# ax12.net
KiCad netlist of a schematic drawn in EAGLE
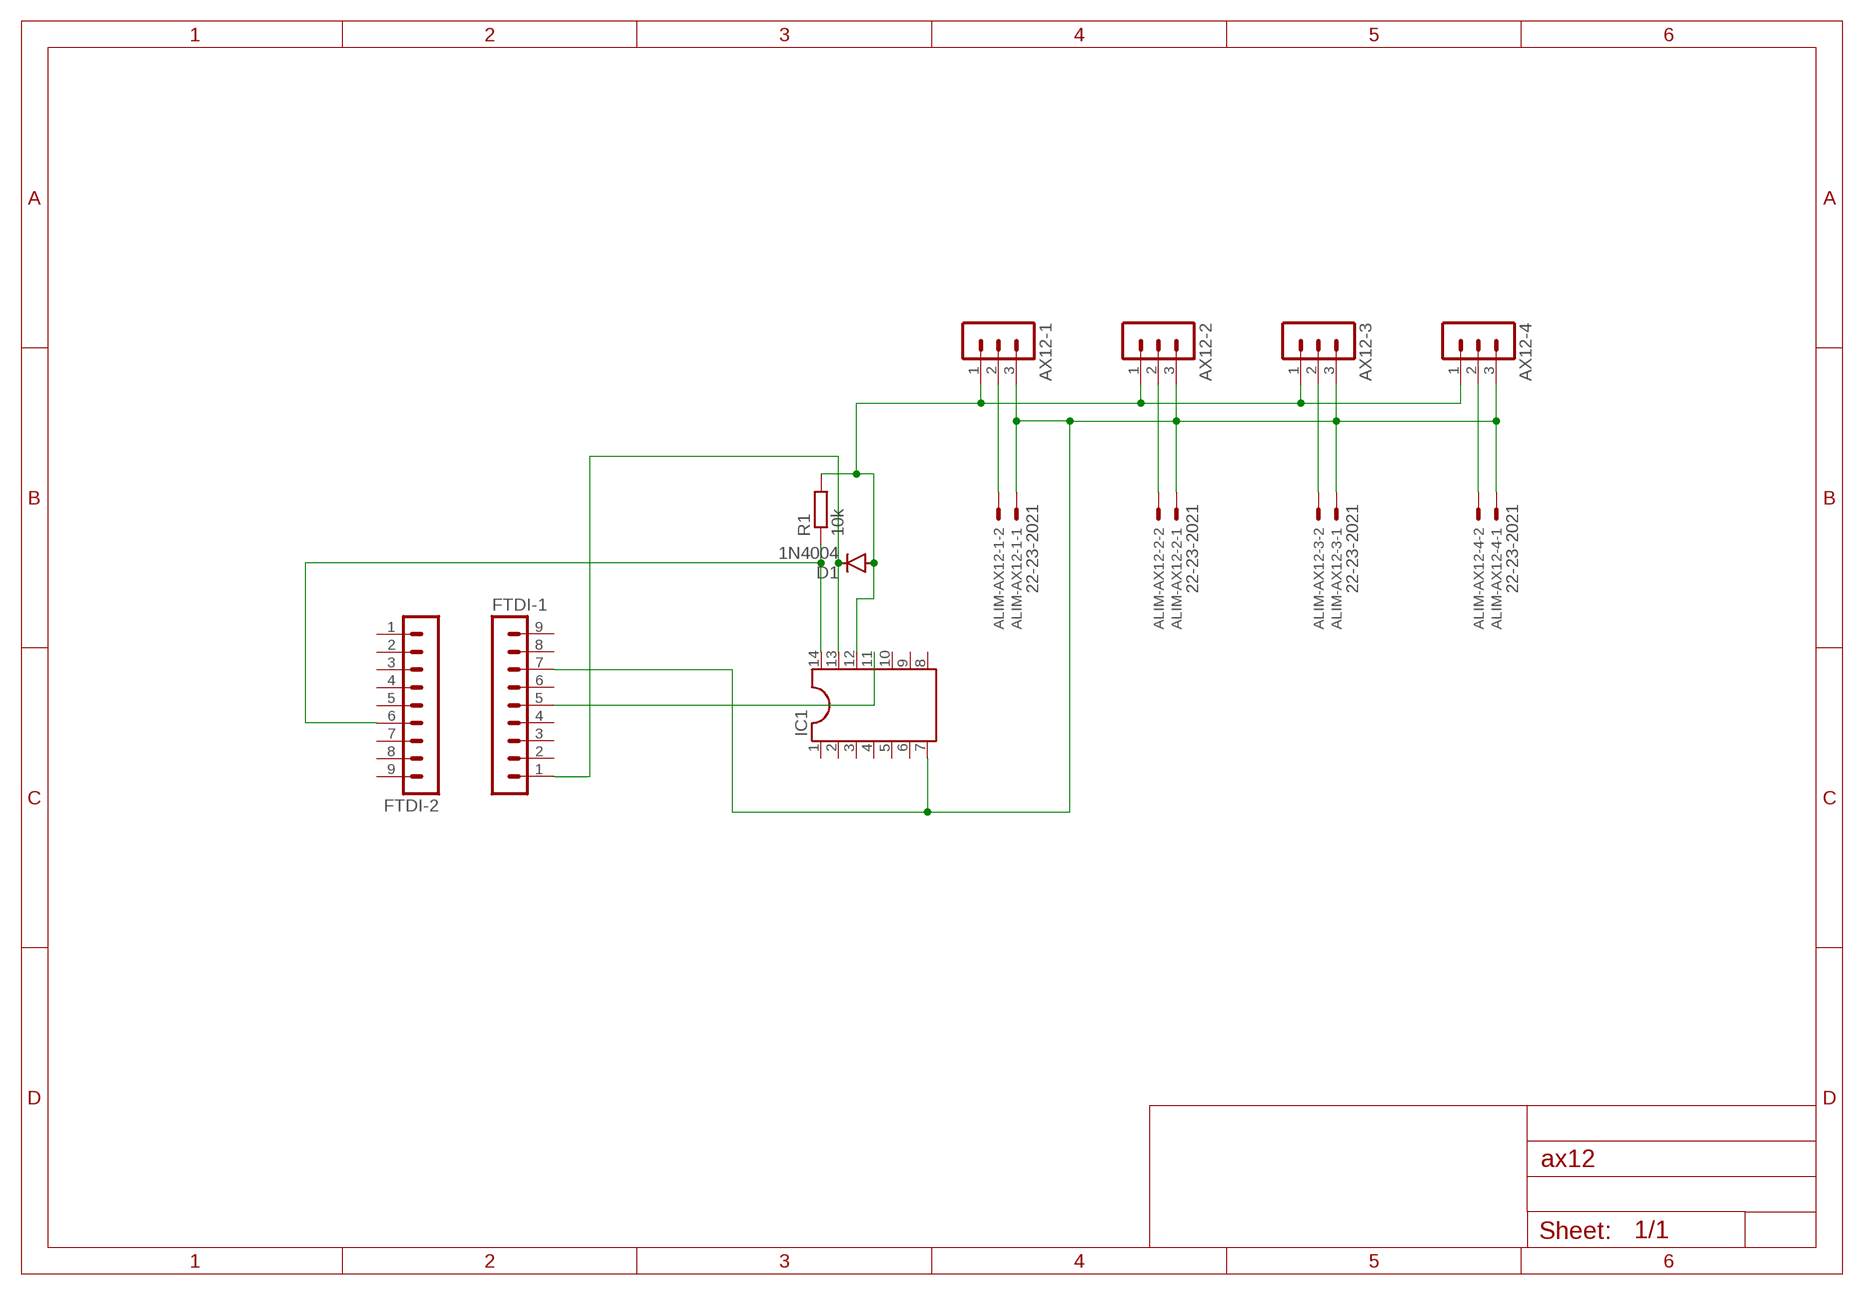
[diagram p0: schematic, sheet 1]

(export (version "E")
  (design (tool "Eeschema 10.0.6"))
  (components
    (comp (ref "ALIM-AX12-1")
      (value "22-23-2021")
      (footprint "eagle-import:22-23-2021")
      (fields (field (name "MF") "MOLEX"))
      (libsource (lib "eagle-import") (part "22-23-2021"))
    )
    (comp (ref "ALIM-AX12-2")
      (value "22-23-2021")
      (footprint "eagle-import:22-23-2021")
      (fields (field (name "MF") "MOLEX"))
      (libsource (lib "eagle-import") (part "22-23-2021"))
    )
    (comp (ref "ALIM-AX12-3")
      (value "22-23-2021")
      (footprint "eagle-import:22-23-2021")
      (fields (field (name "MF") "MOLEX"))
      (libsource (lib "eagle-import") (part "22-23-2021"))
    )
    (comp (ref "ALIM-AX12-4")
      (value "22-23-2021")
      (footprint "eagle-import:22-23-2021")
      (fields (field (name "MF") "MOLEX"))
      (libsource (lib "eagle-import") (part "22-23-2021"))
    )
    (comp (ref "AX12-1")
      (value "MA03-1")
      (footprint "eagle-import:MA03-1")
      (libsource (lib "eagle-import") (part "MA03-1"))
    )
    (comp (ref "AX12-2")
      (value "MA03-1")
      (footprint "eagle-import:MA03-1")
      (libsource (lib "eagle-import") (part "MA03-1"))
    )
    (comp (ref "AX12-3")
      (value "MA03-1")
      (footprint "eagle-import:MA03-1")
      (libsource (lib "eagle-import") (part "MA03-1"))
    )
    (comp (ref "AX12-4")
      (value "MA03-1")
      (footprint "eagle-import:MA03-1")
      (libsource (lib "eagle-import") (part "MA03-1"))
    )
    (comp (ref "D1")
      (value "1N4004")
      (footprint "eagle-import:DO41-10")
      (libsource (lib "eagle-import") (part "1N4004"))
    )
    (comp (ref "FTDI-1")
      (value "MA09-1")
      (footprint "eagle-import:MA09-1")
      (libsource (lib "eagle-import") (part "MA09-1"))
    )
    (comp (ref "FTDI-2")
      (value "MA09-1")
      (footprint "eagle-import:MA09-1")
      (libsource (lib "eagle-import") (part "MA09-1"))
    )
    (comp (ref "IC1")
      (value "DIL14")
      (footprint "eagle-import:DIL14")
      (libsource (lib "eagle-import") (part "DIL14"))
    )
    (comp (ref "R1")
      (value "10k")
      (footprint "eagle-import:0207_12")
      (libsource (lib "eagle-import") (part "R-EU_0207/12"))
    )
  )
  (nets
    (net (code "1") (name "Net-(ALIM-AX12-1A-S)") (class "Default")
      (node (ref "ALIM-AX12-1") (pin "1") (pinfunction "S_1") (pintype "passive"))
      (node (ref "ALIM-AX12-2") (pin "1") (pinfunction "S_1") (pintype "passive"))
      (node (ref "ALIM-AX12-3") (pin "1") (pinfunction "S_1") (pintype "passive"))
      (node (ref "ALIM-AX12-4") (pin "1") (pinfunction "S_1") (pintype "passive"))
      (node (ref "AX12-1") (pin "3") (pinfunction "3_3") (pintype "passive"))
      (node (ref "AX12-2") (pin "3") (pinfunction "3_3") (pintype "passive"))
      (node (ref "AX12-3") (pin "3") (pinfunction "3_3") (pintype "passive"))
      (node (ref "AX12-4") (pin "3") (pinfunction "3_3") (pintype "passive"))
      (node (ref "FTDI-1") (pin "7") (pinfunction "7_7") (pintype "passive"))
      (node (ref "IC1") (pin "7") (pinfunction "7_7") (pintype "passive"))
    )
    (net (code "2") (name "Net-(ALIM-AX12-1B-S)") (class "Default")
      (node (ref "ALIM-AX12-1") (pin "2") (pinfunction "S_2") (pintype "passive"))
      (node (ref "AX12-1") (pin "2") (pinfunction "2_2") (pintype "passive"))
    )
    (net (code "3") (name "Net-(ALIM-AX12-2B-S)") (class "Default")
      (node (ref "ALIM-AX12-2") (pin "2") (pinfunction "S_2") (pintype "passive"))
      (node (ref "AX12-2") (pin "2") (pinfunction "2_2") (pintype "passive"))
    )
    (net (code "4") (name "Net-(ALIM-AX12-3B-S)") (class "Default")
      (node (ref "ALIM-AX12-3") (pin "2") (pinfunction "S_2") (pintype "passive"))
      (node (ref "AX12-3") (pin "2") (pinfunction "2_2") (pintype "passive"))
    )
    (net (code "5") (name "Net-(ALIM-AX12-4B-S)") (class "Default")
      (node (ref "ALIM-AX12-4") (pin "2") (pinfunction "S_2") (pintype "passive"))
      (node (ref "AX12-4") (pin "2") (pinfunction "2_2") (pintype "passive"))
    )
    (net (code "6") (name "Net-(AX12-1-Pad1)") (class "Default")
      (node (ref "AX12-1") (pin "1") (pinfunction "1_1") (pintype "passive"))
      (node (ref "AX12-2") (pin "1") (pinfunction "1_1") (pintype "passive"))
      (node (ref "AX12-3") (pin "1") (pinfunction "1_1") (pintype "passive"))
      (node (ref "AX12-4") (pin "1") (pinfunction "1_1") (pintype "passive"))
      (node (ref "D1") (pin "A") (pinfunction "A_A") (pintype "passive"))
      (node (ref "IC1") (pin "12") (pinfunction "12_12") (pintype "passive"))
      (node (ref "R1") (pin "2") (pinfunction "2_2") (pintype "passive"))
    )
    (net (code "7") (name "Net-(D1-PadC)") (class "Default")
      (node (ref "D1") (pin "C") (pinfunction "C_C") (pintype "passive"))
      (node (ref "FTDI-1") (pin "1") (pinfunction "1_1") (pintype "passive"))
      (node (ref "IC1") (pin "13") (pinfunction "13_13") (pintype "passive"))
    )
    (net (code "8") (name "Net-(FTDI-1-Pad5)") (class "Default")
      (node (ref "FTDI-1") (pin "5") (pinfunction "5_5") (pintype "passive"))
      (node (ref "IC1") (pin "11") (pinfunction "11_11") (pintype "passive"))
    )
    (net (code "9") (name "Net-(FTDI-2-Pad6)") (class "Default")
      (node (ref "FTDI-2") (pin "6") (pinfunction "6_6") (pintype "passive"))
      (node (ref "IC1") (pin "14") (pinfunction "14_14") (pintype "passive"))
      (node (ref "R1") (pin "1") (pinfunction "1_1") (pintype "passive"))
    )
    (net (code "10") (name "unconnected-(FTDI-1-Pad2)") (class "Default")
      (node (ref "FTDI-1") (pin "2") (pinfunction "2_2") (pintype "passive"))
    )
    (net (code "11") (name "unconnected-(FTDI-1-Pad3)") (class "Default")
      (node (ref "FTDI-1") (pin "3") (pinfunction "3_3") (pintype "passive"))
    )
    (net (code "12") (name "unconnected-(FTDI-1-Pad4)") (class "Default")
      (node (ref "FTDI-1") (pin "4") (pinfunction "4_4") (pintype "passive"))
    )
    (net (code "13") (name "unconnected-(FTDI-1-Pad6)") (class "Default")
      (node (ref "FTDI-1") (pin "6") (pinfunction "6_6") (pintype "passive"))
    )
    (net (code "14") (name "unconnected-(FTDI-1-Pad8)") (class "Default")
      (node (ref "FTDI-1") (pin "8") (pinfunction "8_8") (pintype "passive"))
    )
    (net (code "15") (name "unconnected-(FTDI-1-Pad9)") (class "Default")
      (node (ref "FTDI-1") (pin "9") (pinfunction "9_9") (pintype "passive"))
    )
    (net (code "16") (name "unconnected-(FTDI-2-Pad1)") (class "Default")
      (node (ref "FTDI-2") (pin "1") (pinfunction "1_1") (pintype "passive"))
    )
    (net (code "17") (name "unconnected-(FTDI-2-Pad2)") (class "Default")
      (node (ref "FTDI-2") (pin "2") (pinfunction "2_2") (pintype "passive"))
    )
    (net (code "18") (name "unconnected-(FTDI-2-Pad3)") (class "Default")
      (node (ref "FTDI-2") (pin "3") (pinfunction "3_3") (pintype "passive"))
    )
    (net (code "19") (name "unconnected-(FTDI-2-Pad4)") (class "Default")
      (node (ref "FTDI-2") (pin "4") (pinfunction "4_4") (pintype "passive"))
    )
    (net (code "20") (name "unconnected-(FTDI-2-Pad5)") (class "Default")
      (node (ref "FTDI-2") (pin "5") (pinfunction "5_5") (pintype "passive"))
    )
    (net (code "21") (name "unconnected-(FTDI-2-Pad7)") (class "Default")
      (node (ref "FTDI-2") (pin "7") (pinfunction "7_7") (pintype "passive"))
    )
    (net (code "22") (name "unconnected-(FTDI-2-Pad8)") (class "Default")
      (node (ref "FTDI-2") (pin "8") (pinfunction "8_8") (pintype "passive"))
    )
    (net (code "23") (name "unconnected-(FTDI-2-Pad9)") (class "Default")
      (node (ref "FTDI-2") (pin "9") (pinfunction "9_9") (pintype "passive"))
    )
    (net (code "24") (name "unconnected-(IC1-Pad1)") (class "Default")
      (node (ref "IC1") (pin "1") (pinfunction "1_1") (pintype "passive"))
    )
    (net (code "25") (name "unconnected-(IC1-Pad2)") (class "Default")
      (node (ref "IC1") (pin "2") (pinfunction "2_2") (pintype "passive"))
    )
    (net (code "26") (name "unconnected-(IC1-Pad3)") (class "Default")
      (node (ref "IC1") (pin "3") (pinfunction "3_3") (pintype "passive"))
    )
    (net (code "27") (name "unconnected-(IC1-Pad4)") (class "Default")
      (node (ref "IC1") (pin "4") (pinfunction "4_4") (pintype "passive"))
    )
    (net (code "28") (name "unconnected-(IC1-Pad5)") (class "Default")
      (node (ref "IC1") (pin "5") (pinfunction "5_5") (pintype "passive"))
    )
    (net (code "29") (name "unconnected-(IC1-Pad6)") (class "Default")
      (node (ref "IC1") (pin "6") (pinfunction "6_6") (pintype "passive"))
    )
    (net (code "30") (name "unconnected-(IC1-Pad8)") (class "Default")
      (node (ref "IC1") (pin "8") (pinfunction "8_8") (pintype "passive"))
    )
    (net (code "31") (name "unconnected-(IC1-Pad9)") (class "Default")
      (node (ref "IC1") (pin "9") (pinfunction "9_9") (pintype "passive"))
    )
    (net (code "32") (name "unconnected-(IC1-Pad10)") (class "Default")
      (node (ref "IC1") (pin "10") (pinfunction "10_10") (pintype "passive"))
    )
  )
)
